# USB3toTF.net
KiCad netlist of a schematic drawn in Altium Designer
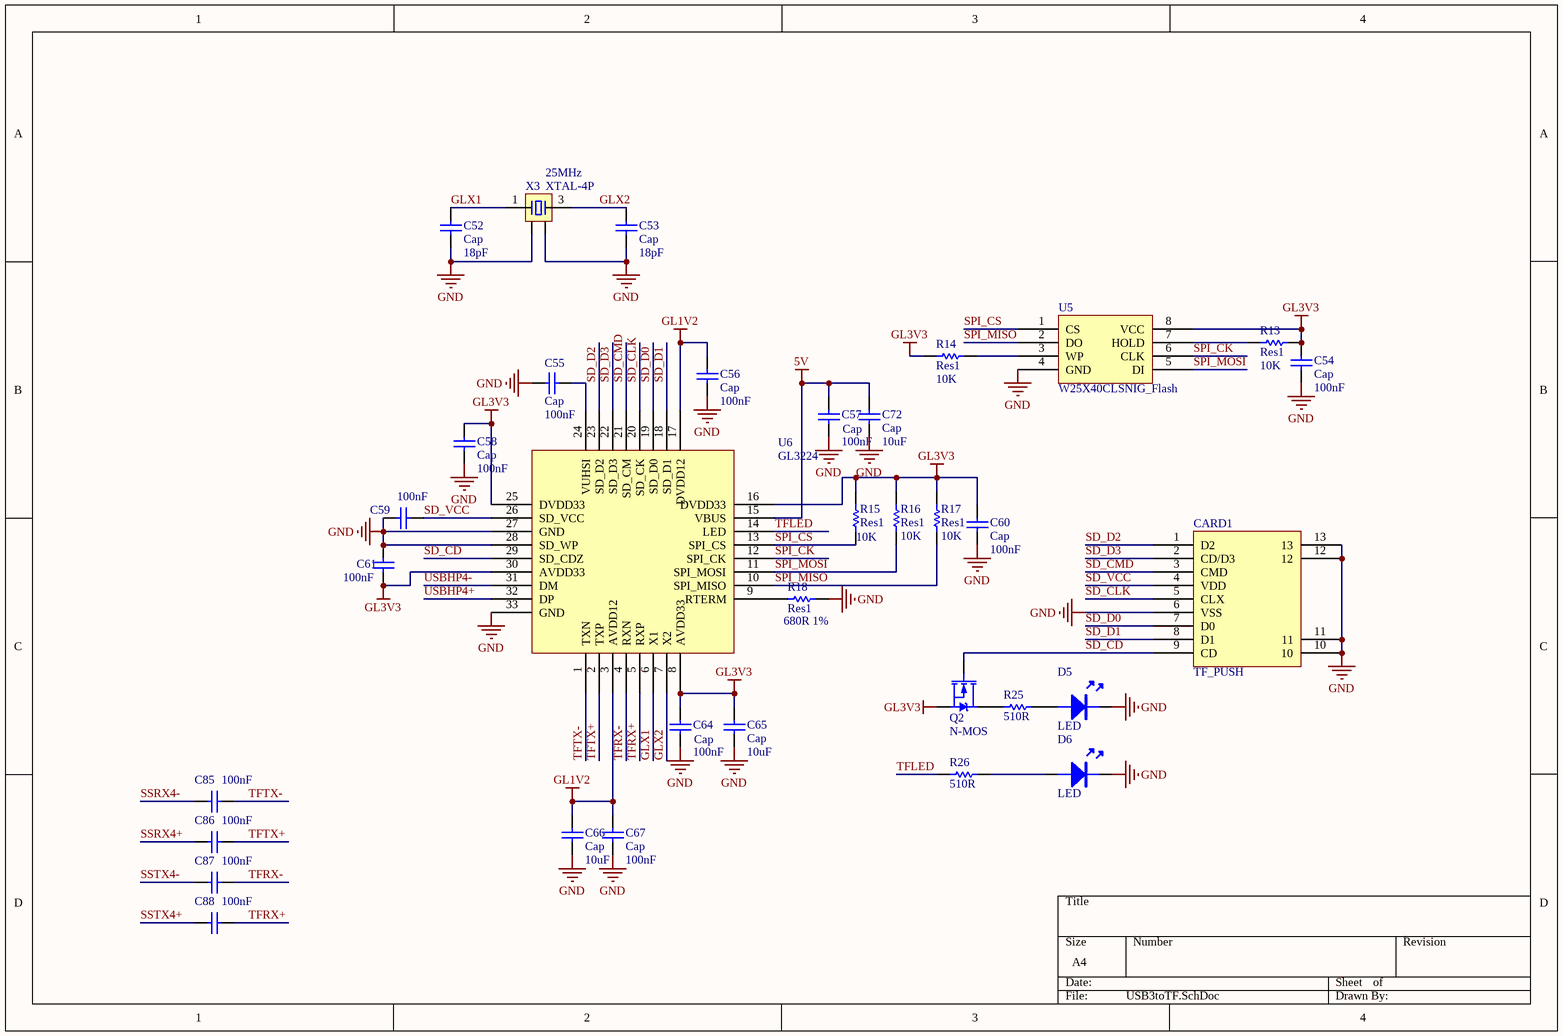
[diagram p0: USB3toTF.SchDoc]

(export (version "E")
  (design (tool "Eeschema 10.0.6"))
  (components
    (comp (ref "C52")
      (value "Cap")
      (footprint "C0603_M")
      (description "Capacitor")
      (fields (field (name "ALTIUM_VALUE") "18pF") (field (name "PUBLISHER") "Altium Limited"))
      (libsource (lib "Miscellaneous Devices") (part "Cap"))
    )
    (comp (ref "C53")
      (value "Cap")
      (footprint "C0603_M")
      (description "Capacitor")
      (fields (field (name "ALTIUM_VALUE") "18pF") (field (name "PUBLISHER") "Altium Limited"))
      (libsource (lib "Miscellaneous Devices") (part "Cap"))
    )
    (comp (ref "C54")
      (value "Cap")
      (footprint "C0603_M")
      (description "Capacitor")
      (fields (field (name "ALTIUM_VALUE") "100nF") (field (name "PUBLISHER") "Altium Limited"))
      (libsource (lib "Miscellaneous Devices") (part "Cap"))
    )
    (comp (ref "C55")
      (value "Cap")
      (footprint "C0603_M")
      (description "Capacitor")
      (fields (field (name "ALTIUM_VALUE") "100nF") (field (name "PUBLISHER") "Altium Limited"))
      (libsource (lib "Miscellaneous Devices") (part "Cap"))
    )
    (comp (ref "C56")
      (value "Cap")
      (footprint "C0603_M")
      (description "Capacitor")
      (fields (field (name "ALTIUM_VALUE") "100nF") (field (name "PUBLISHER") "Altium Limited"))
      (libsource (lib "Miscellaneous Devices") (part "Cap"))
    )
    (comp (ref "C57")
      (value "Cap")
      (footprint "C0603_M")
      (description "Capacitor")
      (fields (field (name "ALTIUM_VALUE") "100nF") (field (name "PUBLISHER") "Altium Limited"))
      (libsource (lib "Miscellaneous Devices") (part "Cap"))
    )
    (comp (ref "C58")
      (value "Cap")
      (footprint "C0603_M")
      (description "Capacitor")
      (fields (field (name "ALTIUM_VALUE") "100nF") (field (name "PUBLISHER") "Altium Limited"))
      (libsource (lib "Miscellaneous Devices") (part "Cap"))
    )
    (comp (ref "C59")
      (value "100nF")
      (footprint "C0603_M")
      (description "Capacitor")
      (fields (field (name "Comment") "Cap") (field (name "PUBLISHER") "Altium Limited"))
      (libsource (lib "Miscellaneous Devices") (part "Cap"))
    )
    (comp (ref "C60")
      (value "Cap")
      (footprint "C0603_M")
      (description "Capacitor")
      (fields (field (name "ALTIUM_VALUE") "100nF") (field (name "PUBLISHER") "Altium Limited"))
      (libsource (lib "Miscellaneous Devices") (part "Cap"))
    )
    (comp (ref "C61")
      (value "100nF")
      (footprint "C0603_M")
      (description "Capacitor")
      (fields (field (name "Comment") "Cap") (field (name "PUBLISHER") "Altium Limited"))
      (libsource (lib "Miscellaneous Devices") (part "Cap"))
    )
    (comp (ref "C64")
      (value "Cap")
      (footprint "C0603_M")
      (description "Capacitor")
      (fields (field (name "ALTIUM_VALUE") "100nF") (field (name "PUBLISHER") "Altium Limited"))
      (libsource (lib "Miscellaneous Devices") (part "Cap"))
    )
    (comp (ref "C65")
      (value "Cap")
      (footprint "C0603_M")
      (description "Capacitor")
      (fields (field (name "ALTIUM_VALUE") "10uF") (field (name "PUBLISHER") "Altium Limited"))
      (libsource (lib "Miscellaneous Devices") (part "Cap"))
    )
    (comp (ref "C66")
      (value "Cap")
      (footprint "C0603_M")
      (description "Capacitor")
      (fields (field (name "ALTIUM_VALUE") "10uF") (field (name "PUBLISHER") "Altium Limited"))
      (libsource (lib "Miscellaneous Devices") (part "Cap"))
    )
    (comp (ref "C67")
      (value "Cap")
      (footprint "C0603_M")
      (description "Capacitor")
      (fields (field (name "ALTIUM_VALUE") "100nF") (field (name "PUBLISHER") "Altium Limited"))
      (libsource (lib "Miscellaneous Devices") (part "Cap"))
    )
    (comp (ref "C72")
      (value "Cap")
      (footprint "C0603_M")
      (description "Capacitor")
      (fields (field (name "ALTIUM_VALUE") "10uF") (field (name "PUBLISHER") "Altium Limited"))
      (libsource (lib "Miscellaneous Devices") (part "Cap"))
    )
    (comp (ref "C85")
      (value "100nF")
      (footprint "1.03-电容:C0402_M")
      (description "Capacitor")
      (fields (field (name "Comment") "Cap") (field (name "PUBLISHER") "Altium Limited"))
      (libsource (lib "Miscellaneous Devices") (part "Cap"))
    )
    (comp (ref "C86")
      (value "100nF")
      (footprint "1.03-电容:C0402_M")
      (description "Capacitor")
      (fields (field (name "Comment") "Cap") (field (name "PUBLISHER") "Altium Limited"))
      (libsource (lib "Miscellaneous Devices") (part "Cap"))
    )
    (comp (ref "C87")
      (value "100nF")
      (footprint "1.03-电容:C0402_M")
      (description "Capacitor")
      (fields (field (name "Comment") "Cap") (field (name "PUBLISHER") "Altium Limited"))
      (libsource (lib "Miscellaneous Devices") (part "Cap"))
    )
    (comp (ref "C88")
      (value "100nF")
      (footprint "1.03-电容:C0402_M")
      (description "Capacitor")
      (fields (field (name "Comment") "Cap") (field (name "PUBLISHER") "Altium Limited"))
      (libsource (lib "Miscellaneous Devices") (part "Cap"))
    )
    (comp (ref "CARD1")
      (value "TF_PUSH")
      (footprint "MyIntLib:TF-SMD_TF-PUSH")
      (libsource (lib "MyIntLib") (part "TF_PUSH"))
    )
    (comp (ref "D5") (value "LED") (footprint "1.08-LED发光二极管:LED0402_B") (libsource (lib "LED") (part "LED")))
    (comp (ref "D6") (value "LED") (footprint "1.08-LED发光二极管:LED0402_B") (libsource (lib "LED") (part "LED")))
    (comp (ref "Q2")
      (value "N-MOS")
      (footprint "MyPCBLib:SOT-723_L1.2-W0.8-P0.40-LS1.2-BR")
      (description "N沟道场效应管")
      (libsource (lib "MOS管") (part "N-MOS"))
    )
    (comp (ref "R13")
      (value "Res1")
      (footprint "R0603_M")
      (description "Resistor")
      (fields (field (name "ALTIUM_VALUE") "10K") (field (name "PUBLISHER") "Altium Limited"))
      (libsource (lib "Miscellaneous Devices") (part "Res1"))
    )
    (comp (ref "R14")
      (value "Res1")
      (footprint "R0603_M")
      (description "Resistor")
      (fields (field (name "ALTIUM_VALUE") "10K") (field (name "PUBLISHER") "Altium Limited"))
      (libsource (lib "Miscellaneous Devices") (part "Res1"))
    )
    (comp (ref "R15")
      (value "Res1")
      (footprint "R0603_M")
      (description "Resistor")
      (fields (field (name "ALTIUM_VALUE") "10K") (field (name "PUBLISHER") "Altium Limited"))
      (libsource (lib "Miscellaneous Devices") (part "Res1"))
    )
    (comp (ref "R16")
      (value "Res1")
      (footprint "R0603_M")
      (description "Resistor")
      (fields (field (name "ALTIUM_VALUE") "10K") (field (name "PUBLISHER") "Altium Limited"))
      (libsource (lib "Miscellaneous Devices") (part "Res1"))
    )
    (comp (ref "R17")
      (value "Res1")
      (footprint "R0603_M")
      (description "Resistor")
      (fields (field (name "ALTIUM_VALUE") "10K") (field (name "PUBLISHER") "Altium Limited"))
      (libsource (lib "Miscellaneous Devices") (part "Res1"))
    )
    (comp (ref "R18")
      (value "Res1")
      (footprint "R0603_M")
      (description "Resistor")
      (fields (field (name "ALTIUM_VALUE") "680R 1%") (field (name "PUBLISHER") "Altium Limited"))
      (libsource (lib "Miscellaneous Devices") (part "Res1"))
    )
    (comp (ref "R25")
      (value "510R")
      (footprint "R0603_M")
      (description "Resistor")
      (fields (field (name "Comment") "Res1") (field (name "PUBLISHER") "Altium Limited"))
      (libsource (lib "Miscellaneous Devices") (part "Res1"))
    )
    (comp (ref "R26")
      (value "510R")
      (footprint "R0603_M")
      (description "Resistor")
      (fields (field (name "Comment") "Res1") (field (name "PUBLISHER") "Altium Limited"))
      (libsource (lib "Miscellaneous Devices") (part "Res1"))
    )
    (comp (ref "U5")
      (value "W25X40CLSNIG_Flash")
      (footprint "2.00-DIP-SOP、SOIC、ESOP、TSSOP、ETSSOP封装:SOP8_M")
      (libsource (lib "MyIntLib") (part "W25X40CLSNIG_Flash"))
    )
    (comp (ref "U6")
      (value "GL3224")
      (footprint "2.04-QFN-UFQFPN-VFQFPN封装:QFN32 5x5_M")
      (libsource (lib "MyIntLib") (part "GL3224"))
    )
    (comp (ref "X3")
      (value "XTAL-4P")
      (footprint "OSC 3225-4P")
      (description "4脚无源晶振")
      (fields (field (name "PARAMETER 1") "25MHz"))
      (libsource (lib "晶振") (part "XTAL-4P"))
    )
  )
  (nets
    (net (code "1") (name "/GLX1") (class "Default")
      (node (ref "C52") (pin "1") (pinfunction "1_1") (pintype "passive"))
      (node (ref "U6") (pin "6") (pinfunction "X1_6") (pintype "passive"))
      (node (ref "X3") (pin "1") (pinfunction "1_1") (pintype "passive"))
    )
    (net (code "2") (name "/GLX2") (class "Default")
      (node (ref "C53") (pin "1") (pinfunction "1_1") (pintype "passive"))
      (node (ref "U6") (pin "7") (pinfunction "X2_7") (pintype "passive"))
      (node (ref "X3") (pin "3") (pinfunction "3_3") (pintype "passive"))
    )
    (net (code "3") (name "/SD_CD") (class "Default")
      (node (ref "CARD1") (pin "9") (pinfunction "CD_9") (pintype "passive"))
      (node (ref "Q2") (pin "G") (pinfunction "G_G") (pintype "passive"))
      (node (ref "U6") (pin "29") (pinfunction "SD_CDZ_29") (pintype "passive"))
    )
    (net (code "4") (name "/SD_CLK") (class "Default")
      (node (ref "CARD1") (pin "5") (pinfunction "CLX_5") (pintype "passive"))
      (node (ref "U6") (pin "20") (pinfunction "SD_CK_20") (pintype "passive"))
    )
    (net (code "5") (name "/SD_CMD") (class "Default")
      (node (ref "CARD1") (pin "3") (pinfunction "CMD_3") (pintype "passive"))
      (node (ref "U6") (pin "21") (pinfunction "SD_CM_21") (pintype "passive"))
    )
    (net (code "6") (name "/SD_D0") (class "Default")
      (node (ref "CARD1") (pin "7") (pinfunction "D0_7") (pintype "passive"))
      (node (ref "U6") (pin "19") (pinfunction "SD_D0_19") (pintype "passive"))
    )
    (net (code "7") (name "/SD_D1") (class "Default")
      (node (ref "CARD1") (pin "8") (pinfunction "D1_8") (pintype "passive"))
      (node (ref "U6") (pin "18") (pinfunction "SD_D1_18") (pintype "passive"))
    )
    (net (code "8") (name "/SD_D2") (class "Default")
      (node (ref "CARD1") (pin "1") (pinfunction "D2_1") (pintype "passive"))
      (node (ref "U6") (pin "23") (pinfunction "SD_D2_23") (pintype "passive"))
    )
    (net (code "9") (name "/SD_D3") (class "Default")
      (node (ref "CARD1") (pin "2") (pinfunction "CD/D3_2") (pintype "passive"))
      (node (ref "U6") (pin "22") (pinfunction "SD_D3_22") (pintype "passive"))
    )
    (net (code "10") (name "/SD_VCC") (class "Default")
      (node (ref "C59") (pin "1") (pinfunction "1_1") (pintype "passive"))
      (node (ref "CARD1") (pin "4") (pinfunction "VDD_4") (pintype "passive"))
      (node (ref "U6") (pin "26") (pinfunction "SD_VCC_26") (pintype "passive"))
    )
    (net (code "11") (name "/SPI_CK") (class "Default")
      (node (ref "U5") (pin "6") (pinfunction "CLK_6") (pintype "passive"))
      (node (ref "U6") (pin "12") (pinfunction "SPI_CK_12") (pintype "passive"))
    )
    (net (code "12") (name "/SPI_CS") (class "Default")
      (node (ref "R15") (pin "1") (pinfunction "1_1") (pintype "passive"))
      (node (ref "U5") (pin "1") (pinfunction "CS_1") (pintype "passive"))
      (node (ref "U6") (pin "13") (pinfunction "SPI_CS_13") (pintype "passive"))
    )
    (net (code "13") (name "/SPI_MISO") (class "Default")
      (node (ref "R17") (pin "1") (pinfunction "1_1") (pintype "passive"))
      (node (ref "U5") (pin "2") (pinfunction "DO_2") (pintype "passive"))
      (node (ref "U6") (pin "10") (pinfunction "SPI_MISO_10") (pintype "passive"))
    )
    (net (code "14") (name "/SPI_MOSI") (class "Default")
      (node (ref "R16") (pin "1") (pinfunction "1_1") (pintype "passive"))
      (node (ref "U5") (pin "5") (pinfunction "DI_5") (pintype "passive"))
      (node (ref "U6") (pin "11") (pinfunction "SPI_MOSI_11") (pintype "passive"))
    )
    (net (code "15") (name "/SSRX4+") (class "Default")
      (node (ref "C86") (pin "2") (pinfunction "2_2") (pintype "passive"))
    )
    (net (code "16") (name "/SSRX4-") (class "Default")
      (node (ref "C85") (pin "2") (pinfunction "2_2") (pintype "passive"))
    )
    (net (code "17") (name "/SSTX4+") (class "Default")
      (node (ref "C88") (pin "2") (pinfunction "2_2") (pintype "passive"))
    )
    (net (code "18") (name "/SSTX4-") (class "Default")
      (node (ref "C87") (pin "2") (pinfunction "2_2") (pintype "passive"))
    )
    (net (code "19") (name "/TFLED") (class "Default")
      (node (ref "R26") (pin "2") (pinfunction "2_2") (pintype "passive"))
      (node (ref "U6") (pin "14") (pinfunction "LED_14") (pintype "passive"))
    )
    (net (code "20") (name "/TFRX+") (class "Default")
      (node (ref "C88") (pin "1") (pinfunction "1_1") (pintype "passive"))
      (node (ref "U6") (pin "5") (pinfunction "RXP_5") (pintype "passive"))
    )
    (net (code "21") (name "/TFRX-") (class "Default")
      (node (ref "C87") (pin "1") (pinfunction "1_1") (pintype "passive"))
      (node (ref "U6") (pin "4") (pinfunction "RXN_4") (pintype "passive"))
    )
    (net (code "22") (name "/TFTX+") (class "Default")
      (node (ref "C86") (pin "1") (pinfunction "1_1") (pintype "passive"))
      (node (ref "U6") (pin "2") (pinfunction "TXP_2") (pintype "passive"))
    )
    (net (code "23") (name "/TFTX-") (class "Default")
      (node (ref "C85") (pin "1") (pinfunction "1_1") (pintype "passive"))
      (node (ref "U6") (pin "1") (pinfunction "TXN_1") (pintype "passive"))
    )
    (net (code "24") (name "/USBHP4+") (class "Default")
      (node (ref "U6") (pin "32") (pinfunction "DP_32") (pintype "passive"))
    )
    (net (code "25") (name "/USBHP4-") (class "Default")
      (node (ref "U6") (pin "31") (pinfunction "DM_31") (pintype "passive"))
    )
    (net (code "26") (name "5V") (class "Default")
      (node (ref "C57") (pin "1") (pinfunction "1_1") (pintype "passive"))
      (node (ref "C72") (pin "1") (pinfunction "1_1") (pintype "passive"))
      (node (ref "U6") (pin "15") (pinfunction "VBUS_15") (pintype "passive"))
    )
    (net (code "27") (name "GL1V2") (class "Default")
      (node (ref "C56") (pin "2") (pinfunction "2_2") (pintype "passive"))
      (node (ref "C66") (pin "1") (pinfunction "1_1") (pintype "passive"))
      (node (ref "C67") (pin "1") (pinfunction "1_1") (pintype "passive"))
      (node (ref "U6") (pin "17") (pinfunction "DVDD12_17") (pintype "passive"))
      (node (ref "U6") (pin "3") (pinfunction "AVDD12_3") (pintype "passive"))
    )
    (net (code "28") (name "GL3V3") (class "Default")
      (node (ref "C54") (pin "1") (pinfunction "1_1") (pintype "passive"))
      (node (ref "C58") (pin "2") (pinfunction "2_2") (pintype "passive"))
      (node (ref "C60") (pin "2") (pinfunction "2_2") (pintype "passive"))
      (node (ref "C61") (pin "2") (pinfunction "2_2") (pintype "passive"))
      (node (ref "C64") (pin "1") (pinfunction "1_1") (pintype "passive"))
      (node (ref "C65") (pin "1") (pinfunction "1_1") (pintype "passive"))
      (node (ref "Q2") (pin "S") (pinfunction "S_S") (pintype "passive"))
      (node (ref "R13") (pin "2") (pinfunction "2_2") (pintype "passive"))
      (node (ref "R14") (pin "1") (pinfunction "1_1") (pintype "passive"))
      (node (ref "R15") (pin "2") (pinfunction "2_2") (pintype "passive"))
      (node (ref "R16") (pin "2") (pinfunction "2_2") (pintype "passive"))
      (node (ref "R17") (pin "2") (pinfunction "2_2") (pintype "passive"))
      (node (ref "U5") (pin "8") (pinfunction "VCC_8") (pintype "passive"))
      (node (ref "U6") (pin "16") (pinfunction "DVDD33_16") (pintype "passive"))
      (node (ref "U6") (pin "25") (pinfunction "DVDD33_25") (pintype "passive"))
      (node (ref "U6") (pin "30") (pinfunction "AVDD33_30") (pintype "passive"))
      (node (ref "U6") (pin "8") (pinfunction "AVDD33_8") (pintype "passive"))
    )
    (net (code "29") (name "GND") (class "Default")
      (node (ref "C52") (pin "2") (pinfunction "2_2") (pintype "passive"))
      (node (ref "C53") (pin "2") (pinfunction "2_2") (pintype "passive"))
      (node (ref "C54") (pin "2") (pinfunction "2_2") (pintype "passive"))
      (node (ref "C55") (pin "1") (pinfunction "1_1") (pintype "passive"))
      (node (ref "C56") (pin "1") (pinfunction "1_1") (pintype "passive"))
      (node (ref "C57") (pin "2") (pinfunction "2_2") (pintype "passive"))
      (node (ref "C58") (pin "1") (pinfunction "1_1") (pintype "passive"))
      (node (ref "C59") (pin "2") (pinfunction "2_2") (pintype "passive"))
      (node (ref "C60") (pin "1") (pinfunction "1_1") (pintype "passive"))
      (node (ref "C61") (pin "1") (pinfunction "1_1") (pintype "passive"))
      (node (ref "C64") (pin "2") (pinfunction "2_2") (pintype "passive"))
      (node (ref "C65") (pin "2") (pinfunction "2_2") (pintype "passive"))
      (node (ref "C66") (pin "2") (pinfunction "2_2") (pintype "passive"))
      (node (ref "C67") (pin "2") (pinfunction "2_2") (pintype "passive"))
      (node (ref "C72") (pin "2") (pinfunction "2_2") (pintype "passive"))
      (node (ref "CARD1") (pin "10") (pinfunction "10_10") (pintype "passive"))
      (node (ref "CARD1") (pin "11") (pinfunction "11_11") (pintype "passive"))
      (node (ref "CARD1") (pin "12") (pinfunction "12_12") (pintype "passive"))
      (node (ref "CARD1") (pin "13") (pinfunction "13_13") (pintype "passive"))
      (node (ref "CARD1") (pin "6") (pinfunction "VSS_6") (pintype "passive"))
      (node (ref "D5") (pin "K") (pinfunction "K_K") (pintype "passive"))
      (node (ref "D6") (pin "K") (pinfunction "K_K") (pintype "passive"))
      (node (ref "R18") (pin "2") (pinfunction "2_2") (pintype "passive"))
      (node (ref "U5") (pin "4") (pinfunction "GND_4") (pintype "passive"))
      (node (ref "U6") (pin "27") (pinfunction "GND_27") (pintype "passive"))
      (node (ref "U6") (pin "28") (pinfunction "SD_WP_28") (pintype "passive"))
      (node (ref "U6") (pin "33") (pinfunction "GND_33") (pintype "passive"))
      (node (ref "X3") (pin "2") (pinfunction "2_2") (pintype "passive"))
      (node (ref "X3") (pin "4") (pinfunction "4_4") (pintype "passive"))
    )
    (net (code "30") (name "Net-(D5-PadA)") (class "Default")
      (node (ref "D5") (pin "A") (pinfunction "A_A") (pintype "passive"))
      (node (ref "R25") (pin "1") (pinfunction "1_1") (pintype "passive"))
    )
    (net (code "31") (name "Net-(D6-PadA)") (class "Default")
      (node (ref "D6") (pin "A") (pinfunction "A_A") (pintype "passive"))
      (node (ref "R26") (pin "1") (pinfunction "1_1") (pintype "passive"))
    )
    (net (code "32") (name "Net-(Q2-PadD)") (class "Default")
      (node (ref "Q2") (pin "D") (pinfunction "D_D") (pintype "passive"))
      (node (ref "R25") (pin "2") (pinfunction "2_2") (pintype "passive"))
    )
    (net (code "33") (name "Net-(U5-HOLD)") (class "Default")
      (node (ref "R13") (pin "1") (pinfunction "1_1") (pintype "passive"))
      (node (ref "U5") (pin "7") (pinfunction "HOLD_7") (pintype "passive"))
    )
    (net (code "34") (name "Net-(U5-WP)") (class "Default")
      (node (ref "R14") (pin "2") (pinfunction "2_2") (pintype "passive"))
      (node (ref "U5") (pin "3") (pinfunction "WP_3") (pintype "passive"))
    )
    (net (code "35") (name "Net-(U6-RTERM)") (class "Default")
      (node (ref "R18") (pin "1") (pinfunction "1_1") (pintype "passive"))
      (node (ref "U6") (pin "9") (pinfunction "RTERM_9") (pintype "passive"))
    )
    (net (code "36") (name "Net-(U6-VUHSI)") (class "Default")
      (node (ref "C55") (pin "2") (pinfunction "2_2") (pintype "passive"))
      (node (ref "U6") (pin "24") (pinfunction "VUHSI_24") (pintype "passive"))
    )
  )
)
